# OpenAGBoardPart1.net
KiCad netlist of a schematic drawn in Altium Designer
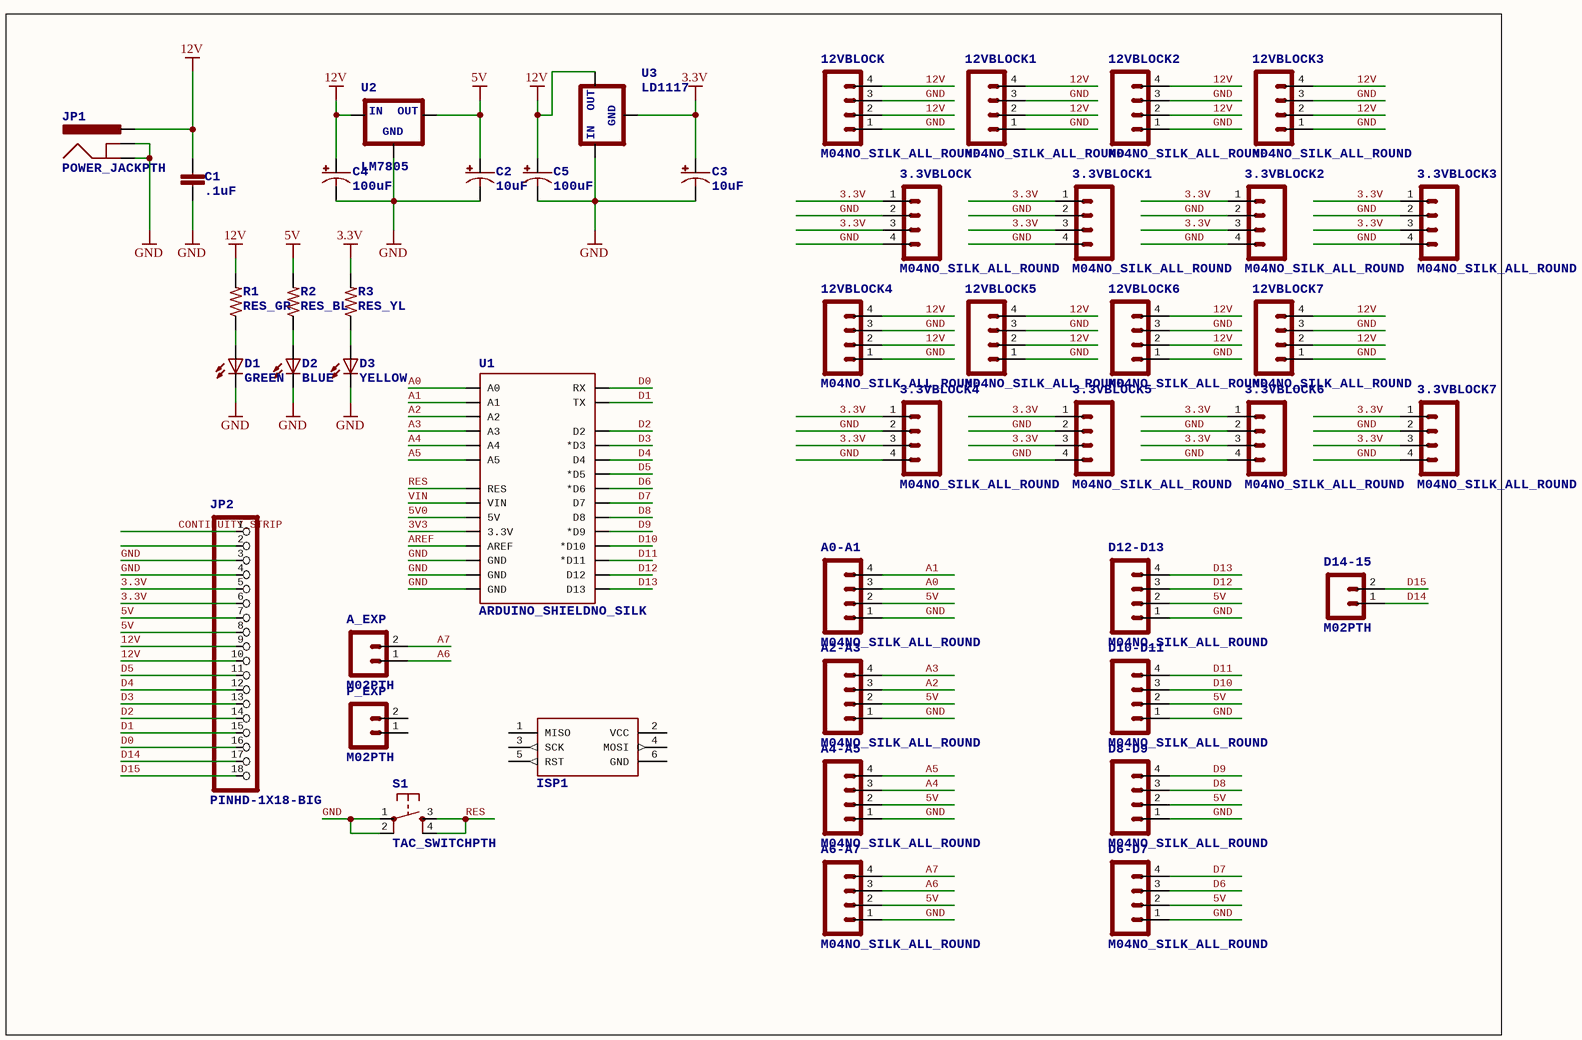
[diagram p0: OpenAGBoardPart1.SchDoc]

(export (version "E")
  (design (tool "Eeschema 10.0.6"))
  (components
    (comp (ref "3.3VBLOCK")
      (value "M04NO_SILK_ALL_ROUND")
      (footprint "1X04_NO_SILK_ALL_ROUND")
      (libsource (lib "SparkFun-Connectors") (part "M04NO_SILK_ALL_ROUND"))
    )
    (comp (ref "3.3VBLOCK1")
      (value "M04NO_SILK_ALL_ROUND")
      (footprint "1X04_NO_SILK_ALL_ROUND")
      (libsource (lib "SparkFun-Connectors") (part "M04NO_SILK_ALL_ROUND"))
    )
    (comp (ref "3.3VBLOCK2")
      (value "M04NO_SILK_ALL_ROUND")
      (footprint "1X04_NO_SILK_ALL_ROUND")
      (libsource (lib "SparkFun-Connectors") (part "M04NO_SILK_ALL_ROUND"))
    )
    (comp (ref "3.3VBLOCK3")
      (value "M04NO_SILK_ALL_ROUND")
      (footprint "1X04_NO_SILK_ALL_ROUND")
      (libsource (lib "SparkFun-Connectors") (part "M04NO_SILK_ALL_ROUND"))
    )
    (comp (ref "3.3VBLOCK4")
      (value "M04NO_SILK_ALL_ROUND")
      (footprint "1X04_NO_SILK_ALL_ROUND")
      (libsource (lib "SparkFun-Connectors") (part "M04NO_SILK_ALL_ROUND"))
    )
    (comp (ref "3.3VBLOCK5")
      (value "M04NO_SILK_ALL_ROUND")
      (footprint "1X04_NO_SILK_ALL_ROUND")
      (libsource (lib "SparkFun-Connectors") (part "M04NO_SILK_ALL_ROUND"))
    )
    (comp (ref "3.3VBLOCK6")
      (value "M04NO_SILK_ALL_ROUND")
      (footprint "1X04_NO_SILK_ALL_ROUND")
      (libsource (lib "SparkFun-Connectors") (part "M04NO_SILK_ALL_ROUND"))
    )
    (comp (ref "3.3VBLOCK7")
      (value "M04NO_SILK_ALL_ROUND")
      (footprint "1X04_NO_SILK_ALL_ROUND")
      (libsource (lib "SparkFun-Connectors") (part "M04NO_SILK_ALL_ROUND"))
    )
    (comp (ref "12VBLOCK")
      (value "M04NO_SILK_ALL_ROUND")
      (footprint "1X04_NO_SILK_ALL_ROUND")
      (libsource (lib "SparkFun-Connectors") (part "M04NO_SILK_ALL_ROUND"))
    )
    (comp (ref "12VBLOCK1")
      (value "M04NO_SILK_ALL_ROUND")
      (footprint "1X04_NO_SILK_ALL_ROUND")
      (libsource (lib "SparkFun-Connectors") (part "M04NO_SILK_ALL_ROUND"))
    )
    (comp (ref "12VBLOCK2")
      (value "M04NO_SILK_ALL_ROUND")
      (footprint "1X04_NO_SILK_ALL_ROUND")
      (libsource (lib "SparkFun-Connectors") (part "M04NO_SILK_ALL_ROUND"))
    )
    (comp (ref "12VBLOCK3")
      (value "M04NO_SILK_ALL_ROUND")
      (footprint "1X04_NO_SILK_ALL_ROUND")
      (libsource (lib "SparkFun-Connectors") (part "M04NO_SILK_ALL_ROUND"))
    )
    (comp (ref "12VBLOCK4")
      (value "M04NO_SILK_ALL_ROUND")
      (footprint "1X04_NO_SILK_ALL_ROUND")
      (libsource (lib "SparkFun-Connectors") (part "M04NO_SILK_ALL_ROUND"))
    )
    (comp (ref "12VBLOCK5")
      (value "M04NO_SILK_ALL_ROUND")
      (footprint "1X04_NO_SILK_ALL_ROUND")
      (libsource (lib "SparkFun-Connectors") (part "M04NO_SILK_ALL_ROUND"))
    )
    (comp (ref "12VBLOCK6")
      (value "M04NO_SILK_ALL_ROUND")
      (footprint "1X04_NO_SILK_ALL_ROUND")
      (libsource (lib "SparkFun-Connectors") (part "M04NO_SILK_ALL_ROUND"))
    )
    (comp (ref "12VBLOCK7")
      (value "M04NO_SILK_ALL_ROUND")
      (footprint "1X04_NO_SILK_ALL_ROUND")
      (libsource (lib "SparkFun-Connectors") (part "M04NO_SILK_ALL_ROUND"))
    )
    (comp (ref "A0-A1")
      (value "M04NO_SILK_ALL_ROUND")
      (footprint "1X04_NO_SILK_ALL_ROUND")
      (libsource (lib "SparkFun-Connectors") (part "M04NO_SILK_ALL_ROUND"))
    )
    (comp (ref "A2-A3")
      (value "M04NO_SILK_ALL_ROUND")
      (footprint "1X04_NO_SILK_ALL_ROUND")
      (libsource (lib "SparkFun-Connectors") (part "M04NO_SILK_ALL_ROUND"))
    )
    (comp (ref "A4-A5")
      (value "M04NO_SILK_ALL_ROUND")
      (footprint "1X04_NO_SILK_ALL_ROUND")
      (libsource (lib "SparkFun-Connectors") (part "M04NO_SILK_ALL_ROUND"))
    )
    (comp (ref "A6-A7")
      (value "M04NO_SILK_ALL_ROUND")
      (footprint "1X04_NO_SILK_ALL_ROUND")
      (libsource (lib "SparkFun-Connectors") (part "M04NO_SILK_ALL_ROUND"))
    )
    (comp (ref "A_EXP")
      (value "M02PTH")
      (footprint "1X02")
      (libsource (lib "SparkFun-Connectors") (part "M02PTH"))
    )
    (comp (ref "C1")
      (value ".1uF")
      (footprint "CAP-PTH-SMALL")
      (description "CapacitorStandard 0603 ceramic capacitor, and 0.1\" leaded capacitor.")
      (libsource (lib "SparkFun-Capacitors") (part "CAPPTH"))
    )
    (comp (ref "C2")
      (value "10uF")
      (footprint "CPOL-RADIAL-10UF-25V")
      (libsource (lib "SparkFun-Passives") (part "CAP_POLPTH2"))
    )
    (comp (ref "C3")
      (value "10uF")
      (footprint "CPOL-RADIAL-10UF-25V")
      (libsource (lib "SparkFun-Passives") (part "CAP_POLPTH2"))
    )
    (comp (ref "C4")
      (value "100uF")
      (footprint "CPOL-RADIAL-100UF-25V")
      (libsource (lib "SparkFun-Passives") (part "CAP_POLPTH1"))
    )
    (comp (ref "C5")
      (value "100uF")
      (footprint "CPOL-RADIAL-100UF-25V")
      (libsource (lib "SparkFun-Passives") (part "CAP_POLPTH1"))
    )
    (comp (ref "D1") (value "GREEN") (footprint "LED5MM") (libsource (lib "adafruit") (part "LED5MM")))
    (comp (ref "D2") (value "BLUE") (footprint "LED5MM") (libsource (lib "adafruit") (part "LED5MM")))
    (comp (ref "D3") (value "YELLOW") (footprint "LED5MM") (libsource (lib "adafruit") (part "LED5MM")))
    (comp (ref "D6-D7")
      (value "M04NO_SILK_ALL_ROUND")
      (footprint "1X04_NO_SILK_ALL_ROUND")
      (libsource (lib "SparkFun-Connectors") (part "M04NO_SILK_ALL_ROUND"))
    )
    (comp (ref "D8-D9")
      (value "M04NO_SILK_ALL_ROUND")
      (footprint "1X04_NO_SILK_ALL_ROUND")
      (libsource (lib "SparkFun-Connectors") (part "M04NO_SILK_ALL_ROUND"))
    )
    (comp (ref "D10-D11")
      (value "M04NO_SILK_ALL_ROUND")
      (footprint "1X04_NO_SILK_ALL_ROUND")
      (libsource (lib "SparkFun-Connectors") (part "M04NO_SILK_ALL_ROUND"))
    )
    (comp (ref "D12-D13")
      (value "M04NO_SILK_ALL_ROUND")
      (footprint "1X04_NO_SILK_ALL_ROUND")
      (libsource (lib "SparkFun-Connectors") (part "M04NO_SILK_ALL_ROUND"))
    )
    (comp (ref "D14-15")
      (value "M02PTH")
      (footprint "1X02")
      (libsource (lib "SparkFun-Connectors") (part "M02PTH"))
    )
    (comp (ref "ISP1")
      (value "AVRISP-6")
      (footprint "AVRISP")
      (description "AVR ISP HEADER Standard 6 pin header for AVR programming")
      (libsource (lib "adafruit") (part "AVRISP-6"))
    )
    (comp (ref "JP1")
      (value "POWER_JACKPTH")
      (footprint "POWER_JACK_PTH")
      (libsource (lib "SparkFun-Connectors") (part "POWER_JACKPTH"))
    )
    (comp (ref "JP2")
      (value "PINHD-1X18-BIG")
      (footprint "1X18-BIG")
      (description "PIN HEADER")
      (libsource (lib "adafruit") (part "PINHD-1X18-BIG"))
    )
    (comp (ref "P_EXP")
      (value "M02PTH")
      (footprint "1X02")
      (libsource (lib "SparkFun-Connectors") (part "M02PTH"))
    )
    (comp (ref "R1")
      (value "RES_GR")
      (footprint "AXIAL-0.4")
      (description "ResistorBasic schematic elements and footprints for 0603, 1206, and PTH resistors.")
      (libsource (lib "SparkFun-Passives") (part "RESISTORPTH-1/4W"))
    )
    (comp (ref "R2")
      (value "RES_BL")
      (footprint "AXIAL-0.4")
      (description "ResistorBasic schematic elements and footprints for 0603, 1206, and PTH resistors.")
      (libsource (lib "SparkFun-Passives") (part "RESISTORPTH-1/4W"))
    )
    (comp (ref "R3")
      (value "RES_YL")
      (footprint "AXIAL-0.4")
      (description "ResistorBasic schematic elements and footprints for 0603, 1206, and PTH resistors.")
      (libsource (lib "SparkFun-Passives") (part "RESISTORPTH-1/4W"))
    )
    (comp (ref "S1")
      (value "TAC_SWITCHPTH")
      (footprint "TACTILE-PTH")
      (libsource (lib "SparkFun-Retired") (part "TAC_SWITCHPTH"))
    )
    (comp (ref "U1")
      (value "ARDUINO_SHIELDNO_SILK")
      (footprint "DUEMILANOVE_VIAS")
      (description "Arduino shield footprint")
      (libsource (lib "SparkFun-Boards") (part "ARDUINO_SHIELDNO_SILK"))
    )
    (comp (ref "U2")
      (value "LM7805")
      (footprint "TO220-IGO")
      (fields (field (name "GND") "GND") (field (name "IN") "IN") (field (name "OUT") "OUT"))
      (libsource (lib "SparkFun-PowerIC") (part "V_REG_78XXSINK"))
    )
    (comp (ref "U3")
      (value "LD1117")
      (footprint "TO220-IGO")
      (fields (field (name "GND") "GND") (field (name "IN") "IN") (field (name "OUT") "OUT"))
      (libsource (lib "SparkFun-PowerIC") (part "V_REG_78XXSINK"))
    )
  )
  (nets
    (net (code "1") (name "/3V3") (class "Default")
      (node (ref "U1") (pin "3.3V") (pinfunction "3.3V_3.3V") (pintype "passive"))
    )
    (net (code "2") (name "/5V0") (class "Default")
      (node (ref "U1") (pin "5V") (pinfunction "5V_5V") (pintype "passive"))
    )
    (net (code "3") (name "/A0") (class "Default")
      (node (ref "A0-A1") (pin "3") (pinfunction "3_3") (pintype "passive"))
      (node (ref "U1") (pin "A0") (pinfunction "A0_A0") (pintype "passive"))
    )
    (net (code "4") (name "/A1") (class "Default")
      (node (ref "A0-A1") (pin "4") (pinfunction "4_4") (pintype "passive"))
      (node (ref "U1") (pin "A1") (pinfunction "A1_A1") (pintype "passive"))
    )
    (net (code "5") (name "/A2") (class "Default")
      (node (ref "A2-A3") (pin "3") (pinfunction "3_3") (pintype "passive"))
      (node (ref "U1") (pin "A2") (pinfunction "A2_A2") (pintype "passive"))
    )
    (net (code "6") (name "/A3") (class "Default")
      (node (ref "A2-A3") (pin "4") (pinfunction "4_4") (pintype "passive"))
      (node (ref "U1") (pin "A3") (pinfunction "A3_A3") (pintype "passive"))
    )
    (net (code "7") (name "/A4") (class "Default")
      (node (ref "A4-A5") (pin "3") (pinfunction "3_3") (pintype "passive"))
      (node (ref "U1") (pin "A4") (pinfunction "A4_A4") (pintype "passive"))
    )
    (net (code "8") (name "/A5") (class "Default")
      (node (ref "A4-A5") (pin "4") (pinfunction "4_4") (pintype "passive"))
      (node (ref "U1") (pin "A5") (pinfunction "A5_A5") (pintype "passive"))
    )
    (net (code "9") (name "/A6") (class "Default")
      (node (ref "A6-A7") (pin "3") (pinfunction "3_3") (pintype "passive"))
      (node (ref "A_EXP") (pin "1") (pinfunction "1_1") (pintype "passive"))
    )
    (net (code "10") (name "/A7") (class "Default")
      (node (ref "A6-A7") (pin "4") (pinfunction "4_4") (pintype "passive"))
      (node (ref "A_EXP") (pin "2") (pinfunction "2_2") (pintype "passive"))
    )
    (net (code "11") (name "/AREF") (class "Default")
      (node (ref "U1") (pin "AREF") (pinfunction "AREF_AREF") (pintype "passive"))
    )
    (net (code "12") (name "/CONTINUITY_STRIP") (class "Default")
      (node (ref "JP2") (pin "1") (pinfunction "1_1") (pintype "passive"))
    )
    (net (code "13") (name "/D0") (class "Default")
      (node (ref "JP2") (pin "16") (pinfunction "16_16") (pintype "passive"))
      (node (ref "U1") (pin "RX") (pinfunction "RX_RX") (pintype "passive"))
    )
    (net (code "14") (name "/D1") (class "Default")
      (node (ref "JP2") (pin "15") (pinfunction "15_15") (pintype "passive"))
      (node (ref "U1") (pin "TX") (pinfunction "TX_TX") (pintype "passive"))
    )
    (net (code "15") (name "/D2") (class "Default")
      (node (ref "JP2") (pin "14") (pinfunction "14_14") (pintype "passive"))
      (node (ref "U1") (pin "D2") (pinfunction "D2_D2") (pintype "passive"))
    )
    (net (code "16") (name "/D3") (class "Default")
      (node (ref "JP2") (pin "13") (pinfunction "13_13") (pintype "passive"))
      (node (ref "U1") (pin "D3") (pinfunction "*D3_D3") (pintype "passive"))
    )
    (net (code "17") (name "/D4") (class "Default")
      (node (ref "JP2") (pin "12") (pinfunction "12_12") (pintype "passive"))
      (node (ref "U1") (pin "D4") (pinfunction "D4_D4") (pintype "passive"))
    )
    (net (code "18") (name "/D5") (class "Default")
      (node (ref "JP2") (pin "11") (pinfunction "11_11") (pintype "passive"))
      (node (ref "U1") (pin "D5") (pinfunction "*D5_D5") (pintype "passive"))
    )
    (net (code "19") (name "/D6") (class "Default")
      (node (ref "D6-D7") (pin "3") (pinfunction "3_3") (pintype "passive"))
      (node (ref "U1") (pin "D6") (pinfunction "*D6_D6") (pintype "passive"))
    )
    (net (code "20") (name "/D7") (class "Default")
      (node (ref "D6-D7") (pin "4") (pinfunction "4_4") (pintype "passive"))
      (node (ref "U1") (pin "D7") (pinfunction "D7_D7") (pintype "passive"))
    )
    (net (code "21") (name "/D8") (class "Default")
      (node (ref "D8-D9") (pin "3") (pinfunction "3_3") (pintype "passive"))
      (node (ref "U1") (pin "D8") (pinfunction "D8_D8") (pintype "passive"))
    )
    (net (code "22") (name "/D9") (class "Default")
      (node (ref "D8-D9") (pin "4") (pinfunction "4_4") (pintype "passive"))
      (node (ref "U1") (pin "D9") (pinfunction "*D9_D9") (pintype "passive"))
    )
    (net (code "23") (name "/D10") (class "Default")
      (node (ref "D10-D11") (pin "3") (pinfunction "3_3") (pintype "passive"))
      (node (ref "U1") (pin "D10") (pinfunction "*D10_D10") (pintype "passive"))
    )
    (net (code "24") (name "/D11") (class "Default")
      (node (ref "D10-D11") (pin "4") (pinfunction "4_4") (pintype "passive"))
      (node (ref "U1") (pin "D11") (pinfunction "*D11_D11") (pintype "passive"))
    )
    (net (code "25") (name "/D12") (class "Default")
      (node (ref "D12-D13") (pin "3") (pinfunction "3_3") (pintype "passive"))
      (node (ref "U1") (pin "D12") (pinfunction "D12_D12") (pintype "passive"))
    )
    (net (code "26") (name "/D13") (class "Default")
      (node (ref "D12-D13") (pin "4") (pinfunction "4_4") (pintype "passive"))
      (node (ref "U1") (pin "D13") (pinfunction "D13_D13") (pintype "passive"))
    )
    (net (code "27") (name "/D14") (class "Default")
      (node (ref "D14-15") (pin "1") (pinfunction "1_1") (pintype "passive"))
      (node (ref "JP2") (pin "17") (pinfunction "17_17") (pintype "passive"))
    )
    (net (code "28") (name "/D15") (class "Default")
      (node (ref "D14-15") (pin "2") (pinfunction "2_2") (pintype "passive"))
      (node (ref "JP2") (pin "18") (pinfunction "18_18") (pintype "passive"))
    )
    (net (code "29") (name "/RES") (class "Default")
      (node (ref "S1") (pin "3") (pinfunction "3_3") (pintype "passive"))
      (node (ref "S1") (pin "4") (pinfunction "4_4") (pintype "passive"))
      (node (ref "U1") (pin "RES") (pinfunction "RES_RES") (pintype "passive"))
    )
    (net (code "30") (name "/VIN") (class "Default")
      (node (ref "U1") (pin "VIN") (pinfunction "VIN_VIN") (pintype "passive"))
    )
    (net (code "31") (name "3.3V") (class "Default")
      (node (ref "3.3VBLOCK") (pin "1") (pinfunction "1_1") (pintype "passive"))
      (node (ref "3.3VBLOCK") (pin "3") (pinfunction "3_3") (pintype "passive"))
      (node (ref "3.3VBLOCK1") (pin "1") (pinfunction "1_1") (pintype "passive"))
      (node (ref "3.3VBLOCK1") (pin "3") (pinfunction "3_3") (pintype "passive"))
      (node (ref "3.3VBLOCK2") (pin "1") (pinfunction "1_1") (pintype "passive"))
      (node (ref "3.3VBLOCK2") (pin "3") (pinfunction "3_3") (pintype "passive"))
      (node (ref "3.3VBLOCK3") (pin "1") (pinfunction "1_1") (pintype "passive"))
      (node (ref "3.3VBLOCK3") (pin "3") (pinfunction "3_3") (pintype "passive"))
      (node (ref "3.3VBLOCK4") (pin "1") (pinfunction "1_1") (pintype "passive"))
      (node (ref "3.3VBLOCK4") (pin "3") (pinfunction "3_3") (pintype "passive"))
      (node (ref "3.3VBLOCK5") (pin "1") (pinfunction "1_1") (pintype "passive"))
      (node (ref "3.3VBLOCK5") (pin "3") (pinfunction "3_3") (pintype "passive"))
      (node (ref "3.3VBLOCK6") (pin "1") (pinfunction "1_1") (pintype "passive"))
      (node (ref "3.3VBLOCK6") (pin "3") (pinfunction "3_3") (pintype "passive"))
      (node (ref "3.3VBLOCK7") (pin "1") (pinfunction "1_1") (pintype "passive"))
      (node (ref "3.3VBLOCK7") (pin "3") (pinfunction "3_3") (pintype "passive"))
      (node (ref "C3") (pin "1") (pinfunction "+_1") (pintype "passive"))
      (node (ref "JP2") (pin "5") (pinfunction "5_5") (pintype "passive"))
      (node (ref "JP2") (pin "6") (pinfunction "6_6") (pintype "passive"))
      (node (ref "R3") (pin "P$2") (pinfunction "2_P$2") (pintype "passive"))
      (node (ref "U3") (pin "GND") (pinfunction "GND_GND") (pintype "passive"))
    )
    (net (code "32") (name "5V") (class "Default")
      (node (ref "A0-A1") (pin "2") (pinfunction "2_2") (pintype "passive"))
      (node (ref "A2-A3") (pin "2") (pinfunction "2_2") (pintype "passive"))
      (node (ref "A4-A5") (pin "2") (pinfunction "2_2") (pintype "passive"))
      (node (ref "A6-A7") (pin "2") (pinfunction "2_2") (pintype "passive"))
      (node (ref "C2") (pin "1") (pinfunction "+_1") (pintype "passive"))
      (node (ref "D10-D11") (pin "2") (pinfunction "2_2") (pintype "passive"))
      (node (ref "D12-D13") (pin "2") (pinfunction "2_2") (pintype "passive"))
      (node (ref "D6-D7") (pin "2") (pinfunction "2_2") (pintype "passive"))
      (node (ref "D8-D9") (pin "2") (pinfunction "2_2") (pintype "passive"))
      (node (ref "JP2") (pin "7") (pinfunction "7_7") (pintype "passive"))
      (node (ref "JP2") (pin "8") (pinfunction "8_8") (pintype "passive"))
      (node (ref "R2") (pin "P$2") (pinfunction "2_P$2") (pintype "passive"))
      (node (ref "U2") (pin "OUT") (pinfunction "OUT_OUT") (pintype "passive"))
    )
    (net (code "33") (name "12V") (class "Default")
      (node (ref "12VBLOCK") (pin "2") (pinfunction "2_2") (pintype "passive"))
      (node (ref "12VBLOCK") (pin "4") (pinfunction "4_4") (pintype "passive"))
      (node (ref "12VBLOCK1") (pin "2") (pinfunction "2_2") (pintype "passive"))
      (node (ref "12VBLOCK1") (pin "4") (pinfunction "4_4") (pintype "passive"))
      (node (ref "12VBLOCK2") (pin "2") (pinfunction "2_2") (pintype "passive"))
      (node (ref "12VBLOCK2") (pin "4") (pinfunction "4_4") (pintype "passive"))
      (node (ref "12VBLOCK3") (pin "2") (pinfunction "2_2") (pintype "passive"))
      (node (ref "12VBLOCK3") (pin "4") (pinfunction "4_4") (pintype "passive"))
      (node (ref "12VBLOCK4") (pin "2") (pinfunction "2_2") (pintype "passive"))
      (node (ref "12VBLOCK4") (pin "4") (pinfunction "4_4") (pintype "passive"))
      (node (ref "12VBLOCK5") (pin "2") (pinfunction "2_2") (pintype "passive"))
      (node (ref "12VBLOCK5") (pin "4") (pinfunction "4_4") (pintype "passive"))
      (node (ref "12VBLOCK6") (pin "2") (pinfunction "2_2") (pintype "passive"))
      (node (ref "12VBLOCK6") (pin "4") (pinfunction "4_4") (pintype "passive"))
      (node (ref "12VBLOCK7") (pin "2") (pinfunction "2_2") (pintype "passive"))
      (node (ref "12VBLOCK7") (pin "4") (pinfunction "4_4") (pintype "passive"))
      (node (ref "C1") (pin "1") (pinfunction "1_1") (pintype "passive"))
      (node (ref "C4") (pin "1") (pinfunction "+_1") (pintype "passive"))
      (node (ref "C5") (pin "1") (pinfunction "+_1") (pintype "passive"))
      (node (ref "JP1") (pin "PWR") (pinfunction "PWR_PWR") (pintype "passive"))
      (node (ref "JP2") (pin "10") (pinfunction "10_10") (pintype "passive"))
      (node (ref "JP2") (pin "9") (pinfunction "9_9") (pintype "passive"))
      (node (ref "R1") (pin "P$2") (pinfunction "2_P$2") (pintype "passive"))
      (node (ref "U2") (pin "IN") (pinfunction "IN_IN") (pintype "passive"))
      (node (ref "U3") (pin "OUT") (pinfunction "OUT_OUT") (pintype "passive"))
    )
    (net (code "34") (name "GND") (class "Default")
      (node (ref "12VBLOCK") (pin "1") (pinfunction "1_1") (pintype "passive"))
      (node (ref "12VBLOCK") (pin "3") (pinfunction "3_3") (pintype "passive"))
      (node (ref "12VBLOCK1") (pin "1") (pinfunction "1_1") (pintype "passive"))
      (node (ref "12VBLOCK1") (pin "3") (pinfunction "3_3") (pintype "passive"))
      (node (ref "12VBLOCK2") (pin "1") (pinfunction "1_1") (pintype "passive"))
      (node (ref "12VBLOCK2") (pin "3") (pinfunction "3_3") (pintype "passive"))
      (node (ref "12VBLOCK3") (pin "1") (pinfunction "1_1") (pintype "passive"))
      (node (ref "12VBLOCK3") (pin "3") (pinfunction "3_3") (pintype "passive"))
      (node (ref "12VBLOCK4") (pin "1") (pinfunction "1_1") (pintype "passive"))
      (node (ref "12VBLOCK4") (pin "3") (pinfunction "3_3") (pintype "passive"))
      (node (ref "12VBLOCK5") (pin "1") (pinfunction "1_1") (pintype "passive"))
      (node (ref "12VBLOCK5") (pin "3") (pinfunction "3_3") (pintype "passive"))
      (node (ref "12VBLOCK6") (pin "1") (pinfunction "1_1") (pintype "passive"))
      (node (ref "12VBLOCK6") (pin "3") (pinfunction "3_3") (pintype "passive"))
      (node (ref "12VBLOCK7") (pin "1") (pinfunction "1_1") (pintype "passive"))
      (node (ref "12VBLOCK7") (pin "3") (pinfunction "3_3") (pintype "passive"))
      (node (ref "3.3VBLOCK") (pin "2") (pinfunction "2_2") (pintype "passive"))
      (node (ref "3.3VBLOCK") (pin "4") (pinfunction "4_4") (pintype "passive"))
      (node (ref "3.3VBLOCK1") (pin "2") (pinfunction "2_2") (pintype "passive"))
      (node (ref "3.3VBLOCK1") (pin "4") (pinfunction "4_4") (pintype "passive"))
      (node (ref "3.3VBLOCK2") (pin "2") (pinfunction "2_2") (pintype "passive"))
      (node (ref "3.3VBLOCK2") (pin "4") (pinfunction "4_4") (pintype "passive"))
      (node (ref "3.3VBLOCK3") (pin "2") (pinfunction "2_2") (pintype "passive"))
      (node (ref "3.3VBLOCK3") (pin "4") (pinfunction "4_4") (pintype "passive"))
      (node (ref "3.3VBLOCK4") (pin "2") (pinfunction "2_2") (pintype "passive"))
      (node (ref "3.3VBLOCK4") (pin "4") (pinfunction "4_4") (pintype "passive"))
      (node (ref "3.3VBLOCK5") (pin "2") (pinfunction "2_2") (pintype "passive"))
      (node (ref "3.3VBLOCK5") (pin "4") (pinfunction "4_4") (pintype "passive"))
      (node (ref "3.3VBLOCK6") (pin "2") (pinfunction "2_2") (pintype "passive"))
      (node (ref "3.3VBLOCK6") (pin "4") (pinfunction "4_4") (pintype "passive"))
      (node (ref "3.3VBLOCK7") (pin "2") (pinfunction "2_2") (pintype "passive"))
      (node (ref "3.3VBLOCK7") (pin "4") (pinfunction "4_4") (pintype "passive"))
      (node (ref "A0-A1") (pin "1") (pinfunction "1_1") (pintype "passive"))
      (node (ref "A2-A3") (pin "1") (pinfunction "1_1") (pintype "passive"))
      (node (ref "A4-A5") (pin "1") (pinfunction "1_1") (pintype "passive"))
      (node (ref "A6-A7") (pin "1") (pinfunction "1_1") (pintype "passive"))
      (node (ref "C1") (pin "2") (pinfunction "2_2") (pintype "passive"))
      (node (ref "C2") (pin "2") (pinfunction "-_2") (pintype "passive"))
      (node (ref "C3") (pin "2") (pinfunction "-_2") (pintype "passive"))
      (node (ref "C4") (pin "2") (pinfunction "-_2") (pintype "passive"))
      (node (ref "C5") (pin "2") (pinfunction "-_2") (pintype "passive"))
      (node (ref "D1") (pin "K") (pinfunction "C_K") (pintype "passive"))
      (node (ref "D10-D11") (pin "1") (pinfunction "1_1") (pintype "passive"))
      (node (ref "D12-D13") (pin "1") (pinfunction "1_1") (pintype "passive"))
      (node (ref "D2") (pin "K") (pinfunction "C_K") (pintype "passive"))
      (node (ref "D3") (pin "K") (pinfunction "C_K") (pintype "passive"))
      (node (ref "D6-D7") (pin "1") (pinfunction "1_1") (pintype "passive"))
      (node (ref "D8-D9") (pin "1") (pinfunction "1_1") (pintype "passive"))
      (node (ref "JP1") (pin "GND") (pinfunction "GND_GND") (pintype "passive"))
      (node (ref "JP1") (pin "GNDBREAK") (pinfunction "GNDBREAK_GNDBREAK") (pintype "passive"))
      (node (ref "JP2") (pin "3") (pinfunction "3_3") (pintype "passive"))
      (node (ref "JP2") (pin "4") (pinfunction "4_4") (pintype "passive"))
      (node (ref "S1") (pin "1") (pinfunction "1_1") (pintype "passive"))
      (node (ref "S1") (pin "2") (pinfunction "2_2") (pintype "passive"))
      (node (ref "U1") (pin "GND@0") (pinfunction "GND_GND@0") (pintype "passive"))
      (node (ref "U1") (pin "GND@1") (pinfunction "GND_GND@1") (pintype "passive"))
      (node (ref "U1") (pin "GND@2") (pinfunction "GND_GND@2") (pintype "passive"))
      (node (ref "U2") (pin "GND") (pinfunction "GND_GND") (pintype "passive"))
      (node (ref "U3") (pin "IN") (pinfunction "IN_IN") (pintype "passive"))
    )
    (net (code "35") (name "Net-(R1-1)") (class "Default")
      (node (ref "D1") (pin "A") (pinfunction "A_A") (pintype "passive"))
      (node (ref "R1") (pin "P$1") (pinfunction "1_P$1") (pintype "passive"))
    )
    (net (code "36") (name "Net-(R2-1)") (class "Default")
      (node (ref "D2") (pin "A") (pinfunction "A_A") (pintype "passive"))
      (node (ref "R2") (pin "P$1") (pinfunction "1_P$1") (pintype "passive"))
    )
    (net (code "37") (name "Net-(R3-1)") (class "Default")
      (node (ref "D3") (pin "A") (pinfunction "A_A") (pintype "passive"))
      (node (ref "R3") (pin "P$1") (pinfunction "1_P$1") (pintype "passive"))
    )
    (net (code "38") (name "unconnected-(ISP1-GND-Pad6)") (class "Default")
      (node (ref "ISP1") (pin "6") (pinfunction "GND_6") (pintype "power_in"))
    )
    (net (code "39") (name "unconnected-(ISP1-MISO-Pad1)") (class "Default")
      (node (ref "ISP1") (pin "1") (pinfunction "MISO_1") (pintype "passive"))
    )
    (net (code "40") (name "unconnected-(ISP1-MOSI-Pad4)") (class "Default")
      (node (ref "ISP1") (pin "4") (pinfunction "MOSI_4") (pintype "output"))
    )
    (net (code "41") (name "unconnected-(ISP1-RST-Pad5)") (class "Default")
      (node (ref "ISP1") (pin "5") (pinfunction "RST_5") (pintype "output"))
    )
    (net (code "42") (name "unconnected-(ISP1-SCK-Pad3)") (class "Default")
      (node (ref "ISP1") (pin "3") (pinfunction "SCK_3") (pintype "output"))
    )
    (net (code "43") (name "unconnected-(ISP1-VCC-Pad2)") (class "Default")
      (node (ref "ISP1") (pin "2") (pinfunction "VCC_2") (pintype "power_in"))
    )
    (net (code "44") (name "unconnected-(JP2-Pad2)") (class "Default")
      (node (ref "JP2") (pin "2") (pinfunction "2_2") (pintype "passive"))
    )
    (net (code "45") (name "unconnected-(P_EXP-Pad1)") (class "Default")
      (node (ref "P_EXP") (pin "1") (pinfunction "1_1") (pintype "passive"))
    )
    (net (code "46") (name "unconnected-(P_EXP-Pad2)") (class "Default")
      (node (ref "P_EXP") (pin "2") (pinfunction "2_2") (pintype "passive"))
    )
  )
)
